# BPS_PowerOutput_v1-0.net
KiCad netlist of a schematic drawn in Altium Designer
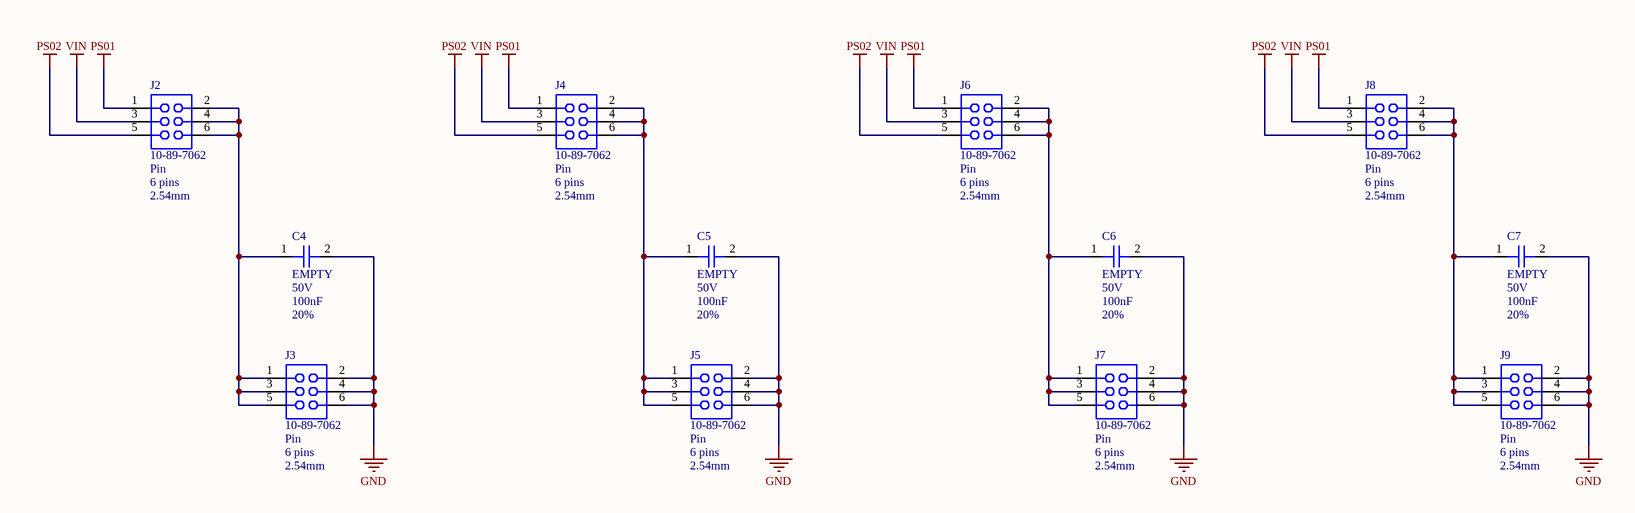
[diagram p0: BPS_PowerOutput_v1-0.SchDoc]

(export (version "E")
  (design (tool "Eeschema 10.0.6"))
  (components
    (comp (ref "C4")
      (value "100nF")
      (footprint "Cap0805")
      (description "Surface Mount Multilayer Ceramic Chip Capacitors  for Commercial Applications")
      (fields
        (field (name "PARTNUMBER1") "EMPTY")
        (field (name "VOLTAGE") "50V")
        (field (name "TOLERANCE") "20%")
        (field (name "Comment") "WCAP-CSGP (0805)")
        (field (name "PUBLISHER") "Lucas Moraes")
      )
      (libsource (lib "CeramicCapacitors") (part "WCAP-CSGP (0805)"))
    )
    (comp (ref "C5")
      (value "100nF")
      (footprint "Cap0805")
      (description "Surface Mount Multilayer Ceramic Chip Capacitors  for Commercial Applications")
      (fields
        (field (name "PARTNUMBER1") "EMPTY")
        (field (name "VOLTAGE") "50V")
        (field (name "TOLERANCE") "20%")
        (field (name "Comment") "WCAP-CSGP (0805)")
        (field (name "PUBLISHER") "Lucas Moraes")
      )
      (libsource (lib "CeramicCapacitors") (part "WCAP-CSGP (0805)"))
    )
    (comp (ref "C6")
      (value "100nF")
      (footprint "Cap0805")
      (description "Surface Mount Multilayer Ceramic Chip Capacitors  for Commercial Applications")
      (fields
        (field (name "PARTNUMBER1") "EMPTY")
        (field (name "VOLTAGE") "50V")
        (field (name "TOLERANCE") "20%")
        (field (name "Comment") "WCAP-CSGP (0805)")
        (field (name "PUBLISHER") "Lucas Moraes")
      )
      (libsource (lib "CeramicCapacitors") (part "WCAP-CSGP (0805)"))
    )
    (comp (ref "C7")
      (value "100nF")
      (footprint "Cap0805")
      (description "Surface Mount Multilayer Ceramic Chip Capacitors  for Commercial Applications")
      (fields
        (field (name "PARTNUMBER1") "EMPTY")
        (field (name "VOLTAGE") "50V")
        (field (name "TOLERANCE") "20%")
        (field (name "Comment") "WCAP-CSGP (0805)")
        (field (name "PUBLISHER") "Lucas Moraes")
      )
      (libsource (lib "CeramicCapacitors") (part "WCAP-CSGP (0805)"))
    )
    (comp (ref "J2")
      (value "10-89-7062")
      (footprint "CONDIL06STRMALE_100_100")
      (description "Headers & Wire Housings C-Grid PCB Conn SR V onn SR Vt Tn-A 8Ckt")
      (fields
        (field (name "PARTNUMBER1") "10-89-7062")
        (field (name "TYPE") "Pin")
        (field (name "PINS") "6 pins")
        (field (name "PITCH") "2.54mm")
        (field (name "PUBLISHER") "Douglas Alves")
      )
      (libsource (lib "Header PinSocket") (part "10-89-7062"))
    )
    (comp (ref "J3")
      (value "10-89-7062")
      (footprint "CONDIL06STRMALE_100_100")
      (description "Headers & Wire Housings C-Grid PCB Conn SR V onn SR Vt Tn-A 8Ckt")
      (fields
        (field (name "PARTNUMBER1") "10-89-7062")
        (field (name "TYPE") "Pin")
        (field (name "PINS") "6 pins")
        (field (name "PITCH") "2.54mm")
        (field (name "PUBLISHER") "Douglas Alves")
      )
      (libsource (lib "Header PinSocket") (part "10-89-7062"))
    )
    (comp (ref "J4")
      (value "10-89-7062")
      (footprint "CONDIL06STRMALE_100_100")
      (description "Headers & Wire Housings C-Grid PCB Conn SR V onn SR Vt Tn-A 8Ckt")
      (fields
        (field (name "PARTNUMBER1") "10-89-7062")
        (field (name "TYPE") "Pin")
        (field (name "PINS") "6 pins")
        (field (name "PITCH") "2.54mm")
        (field (name "PUBLISHER") "Douglas Alves")
      )
      (libsource (lib "Header PinSocket") (part "10-89-7062"))
    )
    (comp (ref "J5")
      (value "10-89-7062")
      (footprint "CONDIL06STRMALE_100_100")
      (description "Headers & Wire Housings C-Grid PCB Conn SR V onn SR Vt Tn-A 8Ckt")
      (fields
        (field (name "PARTNUMBER1") "10-89-7062")
        (field (name "TYPE") "Pin")
        (field (name "PINS") "6 pins")
        (field (name "PITCH") "2.54mm")
        (field (name "PUBLISHER") "Douglas Alves")
      )
      (libsource (lib "Header PinSocket") (part "10-89-7062"))
    )
    (comp (ref "J6")
      (value "10-89-7062")
      (footprint "CONDIL06STRMALE_100_100")
      (description "Headers & Wire Housings C-Grid PCB Conn SR V onn SR Vt Tn-A 8Ckt")
      (fields
        (field (name "PARTNUMBER1") "10-89-7062")
        (field (name "TYPE") "Pin")
        (field (name "PINS") "6 pins")
        (field (name "PITCH") "2.54mm")
        (field (name "PUBLISHER") "Douglas Alves")
      )
      (libsource (lib "Header PinSocket") (part "10-89-7062"))
    )
    (comp (ref "J7")
      (value "10-89-7062")
      (footprint "CONDIL06STRMALE_100_100")
      (description "Headers & Wire Housings C-Grid PCB Conn SR V onn SR Vt Tn-A 8Ckt")
      (fields
        (field (name "PARTNUMBER1") "10-89-7062")
        (field (name "TYPE") "Pin")
        (field (name "PINS") "6 pins")
        (field (name "PITCH") "2.54mm")
        (field (name "PUBLISHER") "Douglas Alves")
      )
      (libsource (lib "Header PinSocket") (part "10-89-7062"))
    )
    (comp (ref "J8")
      (value "10-89-7062")
      (footprint "CONDIL06STRMALE_100_100")
      (description "Headers & Wire Housings C-Grid PCB Conn SR V onn SR Vt Tn-A 8Ckt")
      (fields
        (field (name "PARTNUMBER1") "10-89-7062")
        (field (name "TYPE") "Pin")
        (field (name "PINS") "6 pins")
        (field (name "PITCH") "2.54mm")
        (field (name "PUBLISHER") "Douglas Alves")
      )
      (libsource (lib "Header PinSocket") (part "10-89-7062"))
    )
    (comp (ref "J9")
      (value "10-89-7062")
      (footprint "CONDIL06STRMALE_100_100")
      (description "Headers & Wire Housings C-Grid PCB Conn SR V onn SR Vt Tn-A 8Ckt")
      (fields
        (field (name "PARTNUMBER1") "10-89-7062")
        (field (name "TYPE") "Pin")
        (field (name "PINS") "6 pins")
        (field (name "PITCH") "2.54mm")
        (field (name "PUBLISHER") "Douglas Alves")
      )
      (libsource (lib "Header PinSocket") (part "10-89-7062"))
    )
  )
  (nets
    (net (code "1") (name "GND") (class "Default")
      (node (ref "C4") (pin "2") (pinfunction "2_2") (pintype "passive"))
      (node (ref "C5") (pin "2") (pinfunction "2_2") (pintype "passive"))
      (node (ref "C6") (pin "2") (pinfunction "2_2") (pintype "passive"))
      (node (ref "C7") (pin "2") (pinfunction "2_2") (pintype "passive"))
      (node (ref "J3") (pin "2") (pinfunction "2_2") (pintype "passive"))
      (node (ref "J3") (pin "4") (pinfunction "4_4") (pintype "passive"))
      (node (ref "J3") (pin "6") (pinfunction "6_6") (pintype "passive"))
      (node (ref "J5") (pin "2") (pinfunction "2_2") (pintype "passive"))
      (node (ref "J5") (pin "4") (pinfunction "4_4") (pintype "passive"))
      (node (ref "J5") (pin "6") (pinfunction "6_6") (pintype "passive"))
      (node (ref "J7") (pin "2") (pinfunction "2_2") (pintype "passive"))
      (node (ref "J7") (pin "4") (pinfunction "4_4") (pintype "passive"))
      (node (ref "J7") (pin "6") (pinfunction "6_6") (pintype "passive"))
      (node (ref "J9") (pin "2") (pinfunction "2_2") (pintype "passive"))
      (node (ref "J9") (pin "4") (pinfunction "4_4") (pintype "passive"))
      (node (ref "J9") (pin "6") (pinfunction "6_6") (pintype "passive"))
    )
    (net (code "2") (name "Net-(C4-Pad1)") (class "Default")
      (node (ref "C4") (pin "1") (pinfunction "1_1") (pintype "passive"))
      (node (ref "J2") (pin "2") (pinfunction "2_2") (pintype "passive"))
      (node (ref "J2") (pin "4") (pinfunction "4_4") (pintype "passive"))
      (node (ref "J2") (pin "6") (pinfunction "6_6") (pintype "passive"))
      (node (ref "J3") (pin "1") (pinfunction "1_1") (pintype "passive"))
      (node (ref "J3") (pin "3") (pinfunction "3_3") (pintype "passive"))
      (node (ref "J3") (pin "5") (pinfunction "5_5") (pintype "passive"))
    )
    (net (code "3") (name "Net-(C5-Pad1)") (class "Default")
      (node (ref "C5") (pin "1") (pinfunction "1_1") (pintype "passive"))
      (node (ref "J4") (pin "2") (pinfunction "2_2") (pintype "passive"))
      (node (ref "J4") (pin "4") (pinfunction "4_4") (pintype "passive"))
      (node (ref "J4") (pin "6") (pinfunction "6_6") (pintype "passive"))
      (node (ref "J5") (pin "1") (pinfunction "1_1") (pintype "passive"))
      (node (ref "J5") (pin "3") (pinfunction "3_3") (pintype "passive"))
      (node (ref "J5") (pin "5") (pinfunction "5_5") (pintype "passive"))
    )
    (net (code "4") (name "Net-(C6-Pad1)") (class "Default")
      (node (ref "C6") (pin "1") (pinfunction "1_1") (pintype "passive"))
      (node (ref "J6") (pin "2") (pinfunction "2_2") (pintype "passive"))
      (node (ref "J6") (pin "4") (pinfunction "4_4") (pintype "passive"))
      (node (ref "J6") (pin "6") (pinfunction "6_6") (pintype "passive"))
      (node (ref "J7") (pin "1") (pinfunction "1_1") (pintype "passive"))
      (node (ref "J7") (pin "3") (pinfunction "3_3") (pintype "passive"))
      (node (ref "J7") (pin "5") (pinfunction "5_5") (pintype "passive"))
    )
    (net (code "5") (name "Net-(C7-Pad1)") (class "Default")
      (node (ref "C7") (pin "1") (pinfunction "1_1") (pintype "passive"))
      (node (ref "J8") (pin "2") (pinfunction "2_2") (pintype "passive"))
      (node (ref "J8") (pin "4") (pinfunction "4_4") (pintype "passive"))
      (node (ref "J8") (pin "6") (pinfunction "6_6") (pintype "passive"))
      (node (ref "J9") (pin "1") (pinfunction "1_1") (pintype "passive"))
      (node (ref "J9") (pin "3") (pinfunction "3_3") (pintype "passive"))
      (node (ref "J9") (pin "5") (pinfunction "5_5") (pintype "passive"))
    )
    (net (code "6") (name "PS01") (class "Default")
      (node (ref "J2") (pin "1") (pinfunction "1_1") (pintype "passive"))
      (node (ref "J4") (pin "1") (pinfunction "1_1") (pintype "passive"))
      (node (ref "J6") (pin "1") (pinfunction "1_1") (pintype "passive"))
      (node (ref "J8") (pin "1") (pinfunction "1_1") (pintype "passive"))
    )
    (net (code "7") (name "PS02") (class "Default")
      (node (ref "J2") (pin "5") (pinfunction "5_5") (pintype "passive"))
      (node (ref "J4") (pin "5") (pinfunction "5_5") (pintype "passive"))
      (node (ref "J6") (pin "5") (pinfunction "5_5") (pintype "passive"))
      (node (ref "J8") (pin "5") (pinfunction "5_5") (pintype "passive"))
    )
    (net (code "8") (name "VIN") (class "Default")
      (node (ref "J2") (pin "3") (pinfunction "3_3") (pintype "passive"))
      (node (ref "J4") (pin "3") (pinfunction "3_3") (pintype "passive"))
      (node (ref "J6") (pin "3") (pinfunction "3_3") (pintype "passive"))
      (node (ref "J8") (pin "3") (pinfunction "3_3") (pintype "passive"))
    )
  )
)
